# LEDs.net
KiCad netlist of a schematic drawn in Altium Designer
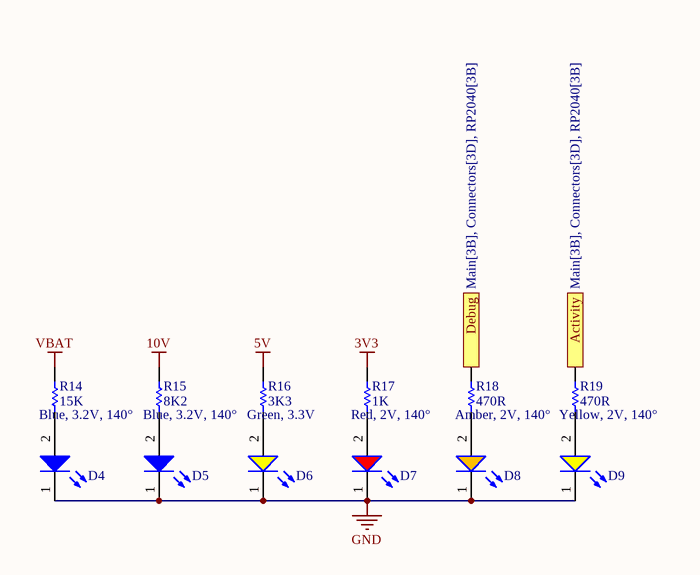
[diagram p0: LEDs.SchDoc]

(export (version "E")
  (design (tool "Eeschema 10.0.6"))
  (components
    (comp (ref "D4")
      (value "Blue, 3.2V, 140°")
      (footprint "WL-SMCW_0603_150060xx75000")
      (description "WL-SMCW Mono-color Chip LED Waterclear, size 0603, Blue, 3.2V, 140°")
      (fields
        (field (name "MANUFACTURER PART NUMBER") "150060BS75000")
        (field (name "MANUFACTURER") "Wurth Elektronik")
      )
      (libsource (lib "Altium_WL-SMCW (rev22d)") (part "150060BS75000"))
    )
    (comp (ref "D5")
      (value "Blue, 3.2V, 140°")
      (footprint "WL-SMCW_0603_150060xx75000")
      (description "WL-SMCW Mono-color Chip LED Waterclear, size 0603, Blue, 3.2V, 140°")
      (fields
        (field (name "MANUFACTURER PART NUMBER") "150060BS75000")
        (field (name "MANUFACTURER") "Wurth Elektronik")
      )
      (libsource (lib "Altium_WL-SMCW (rev22d)") (part "150060BS75000"))
    )
    (comp (ref "D6")
      (value "Green, 3.3V")
      (footprint "WL-SMCW_0603_150060xx75000")
      (description "WL-SMCW Mono-color Chip LED Waterclear, size 0603, Yellow, 2V, 140°")
      (fields
        (field (name "MANUFACTURER PART NUMBER") "150060YS75000")
        (field (name "MANUFACTURER") "Wurth Elektronik")
      )
      (libsource (lib "Altium_WL-SMCW (rev22d)") (part "150060YS75000"))
    )
    (comp (ref "D7")
      (value "Red, 2V, 140°")
      (footprint "WL-SMCW_0603_150060xx75000")
      (description "WL-SMCW Mono-color Chip LED Waterclear, size 0603, Red, 2V, 140°")
      (fields
        (field (name "MANUFACTURER PART NUMBER") "150060RS75000")
        (field (name "MANUFACTURER") "Wurth Elektronik")
      )
      (libsource (lib "Altium_WL-SMCW (rev22d)") (part "150060RS75000"))
    )
    (comp (ref "D8")
      (value "Amber, 2V, 140°")
      (footprint "WL-SMCW_0603_150060xx75000")
      (description "WL-SMCW Mono-color Chip LED Waterclear, size 0603, Amber, 2V, 140°")
      (fields
        (field (name "MANUFACTURER PART NUMBER") "150060AS75000")
        (field (name "MANUFACTURER") "Wurth Elektronik")
      )
      (libsource (lib "Altium_WL-SMCW (rev22d)") (part "150060AS75000"))
    )
    (comp (ref "D9")
      (value "Yellow, 2V, 140°")
      (footprint "WL-SMCW_0603_150060xx75000")
      (description "WL-SMCW Mono-color Chip LED Waterclear, size 0603, Yellow, 2V, 140°")
      (fields
        (field (name "MANUFACTURER PART NUMBER") "150060YS75000")
        (field (name "MANUFACTURER") "Wurth Elektronik")
      )
      (libsource (lib "Altium_WL-SMCW (rev22d)") (part "150060YS75000"))
    )
    (comp (ref "R14")
      (value "15K")
      (footprint "Custom Components:0402 resistor")
      (libsource (lib "Custom Components") (part "Resistor 0402 1K"))
    )
    (comp (ref "R15")
      (value "8K2")
      (footprint "Custom Components:0402 resistor")
      (libsource (lib "Custom Components") (part "Resistor 0402 1K"))
    )
    (comp (ref "R16")
      (value "3K3")
      (footprint "Custom Components:0402 resistor")
      (libsource (lib "Custom Components") (part "Resistor 0402 1K"))
    )
    (comp (ref "R17")
      (value "1K")
      (footprint "Custom Components:0402 resistor")
      (libsource (lib "Custom Components") (part "Resistor 0402 1K"))
    )
    (comp (ref "R18")
      (value "470R")
      (footprint "Custom Components:0402 resistor")
      (libsource (lib "Custom Components") (part "Resistor 0402 1K"))
    )
    (comp (ref "R19")
      (value "470R")
      (footprint "Custom Components:0402 resistor")
      (libsource (lib "Custom Components") (part "Resistor 0402 1K"))
    )
  )
  (nets
    (net (code "1") (name "/Activity") (class "Default")
      (node (ref "R19") (pin "2") (pinfunction "2_2") (pintype "passive"))
    )
    (net (code "2") (name "/Debug") (class "Default")
      (node (ref "R18") (pin "2") (pinfunction "2_2") (pintype "passive"))
    )
    (net (code "3") (name "3V3") (class "Default")
      (node (ref "R17") (pin "2") (pinfunction "2_2") (pintype "passive"))
    )
    (net (code "4") (name "5V") (class "Default")
      (node (ref "R16") (pin "2") (pinfunction "2_2") (pintype "passive"))
    )
    (net (code "5") (name "10V") (class "Default")
      (node (ref "R15") (pin "2") (pinfunction "2_2") (pintype "passive"))
    )
    (net (code "6") (name "GND") (class "Default")
      (node (ref "D4") (pin "1") (pinfunction "K_1") (pintype "passive"))
      (node (ref "D5") (pin "1") (pinfunction "K_1") (pintype "passive"))
      (node (ref "D6") (pin "1") (pinfunction "K_1") (pintype "passive"))
      (node (ref "D7") (pin "1") (pinfunction "K_1") (pintype "passive"))
      (node (ref "D8") (pin "1") (pinfunction "K_1") (pintype "passive"))
      (node (ref "D9") (pin "1") (pinfunction "K_1") (pintype "passive"))
    )
    (net (code "7") (name "Net-(D4-A)") (class "Default")
      (node (ref "D4") (pin "2") (pinfunction "A_2") (pintype "passive"))
      (node (ref "R14") (pin "1") (pinfunction "1_1") (pintype "passive"))
    )
    (net (code "8") (name "Net-(D5-A)") (class "Default")
      (node (ref "D5") (pin "2") (pinfunction "A_2") (pintype "passive"))
      (node (ref "R15") (pin "1") (pinfunction "1_1") (pintype "passive"))
    )
    (net (code "9") (name "Net-(D6-A)") (class "Default")
      (node (ref "D6") (pin "2") (pinfunction "A_2") (pintype "passive"))
      (node (ref "R16") (pin "1") (pinfunction "1_1") (pintype "passive"))
    )
    (net (code "10") (name "Net-(D7-A)") (class "Default")
      (node (ref "D7") (pin "2") (pinfunction "A_2") (pintype "passive"))
      (node (ref "R17") (pin "1") (pinfunction "1_1") (pintype "passive"))
    )
    (net (code "11") (name "Net-(D8-A)") (class "Default")
      (node (ref "D8") (pin "2") (pinfunction "A_2") (pintype "passive"))
      (node (ref "R18") (pin "1") (pinfunction "1_1") (pintype "passive"))
    )
    (net (code "12") (name "Net-(D9-A)") (class "Default")
      (node (ref "D9") (pin "2") (pinfunction "A_2") (pintype "passive"))
      (node (ref "R19") (pin "1") (pinfunction "1_1") (pintype "passive"))
    )
    (net (code "13") (name "VBAT") (class "Default")
      (node (ref "R14") (pin "2") (pinfunction "2_2") (pintype "passive"))
    )
  )
)
